# untitled.net
KiCad netlist of a schematic drawn in EAGLE
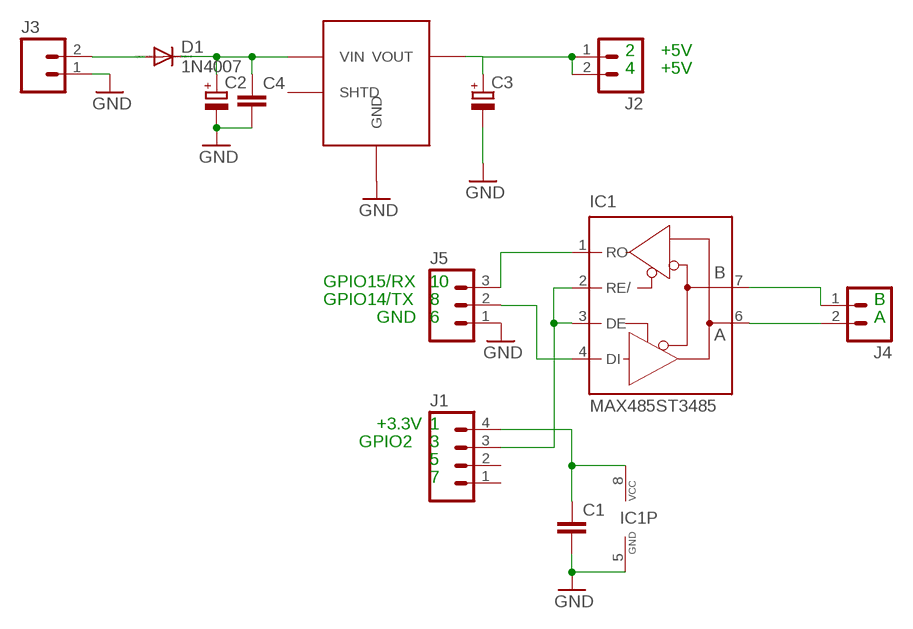
[diagram p0: schematic, sheet 1]

(export (version "E")
  (design (tool "Eeschema 10.0.6"))
  (components
    (comp (ref "C1")
      (value "C-EU050-025X075")
      (footprint "eagle-import:C050-025X075")
      (libsource (lib "eagle-import") (part "C-EU050-025X075"))
    )
    (comp (ref "C2")
      (value "CPOL-EUSMD4X5.3")
      (footprint "eagle-import:UD-4X5,8_NICHICON")
      (libsource (lib "eagle-import") (part "CPOL-EUSMD4X5.3"))
    )
    (comp (ref "C3")
      (value "CPOL-EUSMD4X5.3")
      (footprint "eagle-import:UD-4X5,8_NICHICON")
      (libsource (lib "eagle-import") (part "CPOL-EUSMD4X5.3"))
    )
    (comp (ref "C4")
      (value "C-EU050-025X075")
      (footprint "eagle-import:C050-025X075")
      (libsource (lib "eagle-import") (part "C-EU050-025X075"))
    )
    (comp (ref "D1")
      (value "1N4007")
      (footprint "eagle-import:DO41-10")
      (libsource (lib "eagle-import") (part "1N4007"))
    )
    (comp (ref "IC1")
      (value "MAX485ST3485")
      (footprint "eagle-import:SO08")
      (libsource (lib "eagle-import") (part "MAX485ST3485"))
    )
    (comp (ref "J1")
      (value "M04")
      (footprint "eagle-import:1X04")
      (libsource (lib "eagle-import") (part "M04"))
    )
    (comp (ref "J2")
      (value "M02")
      (footprint "eagle-import:1X02")
      (libsource (lib "eagle-import") (part "M02"))
    )
    (comp (ref "J3")
      (value "M02-SCREW-3.5MM3.5MM")
      (footprint "eagle-import:SCREWTERMINAL-3.5MM-2")
      (libsource (lib "eagle-import") (part "M02-SCREW-3.5MM3.5MM"))
    )
    (comp (ref "J4")
      (value "M02-SCREW-3.5MM3.5MM")
      (footprint "eagle-import:SCREWTERMINAL-3.5MM-2")
      (libsource (lib "eagle-import") (part "M02-SCREW-3.5MM3.5MM"))
    )
    (comp (ref "J5")
      (value "M03")
      (footprint "eagle-import:1X03")
      (libsource (lib "eagle-import") (part "M03"))
    )
    (comp (ref "U$1")
      (value "POLOLU-2098")
      (footprint "eagle-import:POLOLU-10-13")
      (libsource (lib "eagle-import") (part "POLOLU-2098"))
    )
  )
  (nets
    (net (code "1") (name "/SHTD") (class "Default")
      (node (ref "U$1") (pin "P$1") (pinfunction "SHTD_P$1") (pintype "power_in"))
    )
    (net (code "2") (name "GND") (class "Default")
      (node (ref "C1") (pin "2") (pinfunction "2_2") (pintype "passive"))
      (node (ref "C2") (pin "-") (pinfunction "-_-") (pintype "passive"))
      (node (ref "C3") (pin "-") (pinfunction "-_-") (pintype "passive"))
      (node (ref "C4") (pin "2") (pinfunction "2_2") (pintype "passive"))
      (node (ref "IC1") (pin "5") (pinfunction "GND_5") (pintype "power_in"))
      (node (ref "J3") (pin "1") (pinfunction "1_1") (pintype "passive"))
      (node (ref "J5") (pin "1") (pinfunction "1_1") (pintype "passive"))
      (node (ref "U$1") (pin "P$3") (pinfunction "GND_P$3") (pintype "bidirectional"))
    )
    (net (code "3") (name "Net-(D1-PadA)") (class "Default")
      (node (ref "D1") (pin "A") (pinfunction "A_A") (pintype "passive"))
      (node (ref "J3") (pin "2") (pinfunction "2_2") (pintype "passive"))
    )
    (net (code "4") (name "Net-(IC1A-A)") (class "Default")
      (node (ref "IC1") (pin "6") (pinfunction "A_6") (pintype "passive"))
      (node (ref "J4") (pin "2") (pinfunction "2_2") (pintype "passive"))
    )
    (net (code "5") (name "Net-(IC1A-B)") (class "Default")
      (node (ref "IC1") (pin "7") (pinfunction "B_7") (pintype "passive"))
      (node (ref "J4") (pin "1") (pinfunction "1_1") (pintype "passive"))
    )
    (net (code "6") (name "Net-(IC1A-DE)") (class "Default")
      (node (ref "IC1") (pin "2") (pinfunction "RE/_2") (pintype "input"))
      (node (ref "IC1") (pin "3") (pinfunction "DE_3") (pintype "input"))
      (node (ref "J1") (pin "3") (pinfunction "3_3") (pintype "passive"))
    )
    (net (code "7") (name "Net-(IC1A-DI)") (class "Default")
      (node (ref "IC1") (pin "4") (pinfunction "DI_4") (pintype "input"))
      (node (ref "J5") (pin "2") (pinfunction "2_2") (pintype "passive"))
    )
    (net (code "8") (name "Net-(IC1A-RO)") (class "Default")
      (node (ref "IC1") (pin "1") (pinfunction "RO_1") (pintype "output"))
      (node (ref "J5") (pin "3") (pinfunction "3_3") (pintype "passive"))
    )
    (net (code "9") (name "Net-(IC1B-VCC)") (class "Default")
      (node (ref "C1") (pin "1") (pinfunction "1_1") (pintype "passive"))
      (node (ref "IC1") (pin "8") (pinfunction "VCC_8") (pintype "power_in"))
      (node (ref "J1") (pin "4") (pinfunction "4_4") (pintype "passive"))
    )
    (net (code "10") (name "Net-(U$1-VIN)") (class "Default")
      (node (ref "C2") (pin "+") (pinfunction "+_+") (pintype "passive"))
      (node (ref "C4") (pin "1") (pinfunction "1_1") (pintype "passive"))
      (node (ref "D1") (pin "C") (pinfunction "C_C") (pintype "passive"))
      (node (ref "U$1") (pin "P$2") (pinfunction "VIN_P$2") (pintype "power_in"))
    )
    (net (code "11") (name "Net-(U$1-VOUT)") (class "Default")
      (node (ref "C3") (pin "+") (pinfunction "+_+") (pintype "passive"))
      (node (ref "J2") (pin "1") (pinfunction "1_1") (pintype "passive"))
      (node (ref "J2") (pin "2") (pinfunction "2_2") (pintype "passive"))
      (node (ref "U$1") (pin "P$4") (pinfunction "VOUT_P$4") (pintype "bidirectional"))
    )
    (net (code "12") (name "unconnected-(J1-Pad1)") (class "Default")
      (node (ref "J1") (pin "1") (pinfunction "1_1") (pintype "passive"))
    )
    (net (code "13") (name "unconnected-(J1-Pad2)") (class "Default")
      (node (ref "J1") (pin "2") (pinfunction "2_2") (pintype "passive"))
    )
  )
)
